# ADL5801.net
KiCad netlist of a schematic drawn in Altium Designer
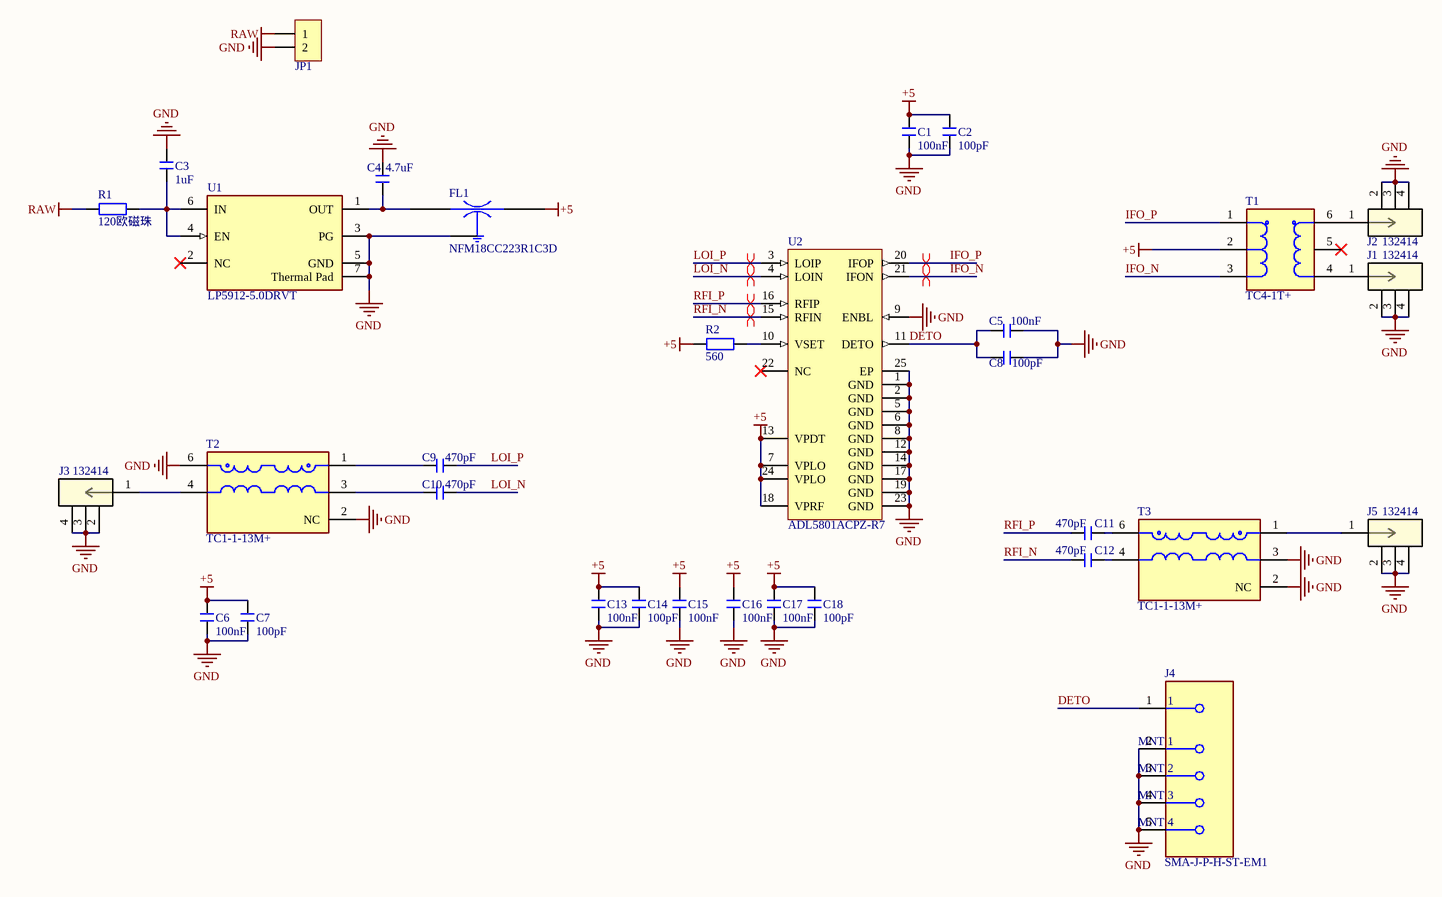
[diagram p0: ADL5801.SchDoc]

(export (version "E")
  (design (tool "Eeschema 10.0.6"))
  (components
    (comp (ref "C1")
      (value "100nF")
      (footprint "C 0402_L")
      (description "贴片电容")
      (libsource (lib "01 - 电容-电阻-电感") (part "C"))
    )
    (comp (ref "C2")
      (value "100pF")
      (footprint "C 0402_L")
      (description "贴片电容")
      (libsource (lib "01 - 电容-电阻-电感") (part "C"))
    )
    (comp (ref "C3")
      (value "1uF")
      (footprint "C 0603_L")
      (description "贴片电容")
      (libsource (lib "01 - 电容-电阻-电感") (part "C"))
    )
    (comp (ref "C4")
      (value "4.7uF")
      (footprint "C 0603_L")
      (description "贴片电容")
      (libsource (lib "01 - 电容-电阻-电感") (part "C"))
    )
    (comp (ref "C5")
      (value "100nF")
      (footprint "C 0402_L")
      (description "贴片电容")
      (libsource (lib "01 - 电容-电阻-电感") (part "C"))
    )
    (comp (ref "C6")
      (value "100nF")
      (footprint "C 0402_L")
      (description "贴片电容")
      (libsource (lib "01 - 电容-电阻-电感") (part "C"))
    )
    (comp (ref "C7")
      (value "100pF")
      (footprint "C 0402_L")
      (description "贴片电容")
      (libsource (lib "01 - 电容-电阻-电感") (part "C"))
    )
    (comp (ref "C8")
      (value "100pF")
      (footprint "C 0402_L")
      (description "贴片电容")
      (libsource (lib "01 - 电容-电阻-电感") (part "C"))
    )
    (comp (ref "C9")
      (value "470pF")
      (footprint "C 0402_L")
      (description "贴片电容")
      (libsource (lib "01 - 电容-电阻-电感") (part "C"))
    )
    (comp (ref "C10")
      (value "470pF")
      (footprint "C 0402_L")
      (description "贴片电容")
      (libsource (lib "01 - 电容-电阻-电感") (part "C"))
    )
    (comp (ref "C11")
      (value "470pF")
      (footprint "C 0402_L")
      (description "贴片电容")
      (libsource (lib "01 - 电容-电阻-电感") (part "C"))
    )
    (comp (ref "C12")
      (value "470pF")
      (footprint "C 0402_L")
      (description "贴片电容")
      (libsource (lib "01 - 电容-电阻-电感") (part "C"))
    )
    (comp (ref "C13")
      (value "100nF")
      (footprint "C 0402_L")
      (description "贴片电容")
      (libsource (lib "01 - 电容-电阻-电感") (part "C"))
    )
    (comp (ref "C14")
      (value "100pF")
      (footprint "C 0402_L")
      (description "贴片电容")
      (libsource (lib "01 - 电容-电阻-电感") (part "C"))
    )
    (comp (ref "C15")
      (value "100nF")
      (footprint "C 0402_L")
      (description "贴片电容")
      (libsource (lib "01 - 电容-电阻-电感") (part "C"))
    )
    (comp (ref "C16")
      (value "100nF")
      (footprint "C 0402_L")
      (description "贴片电容")
      (libsource (lib "01 - 电容-电阻-电感") (part "C"))
    )
    (comp (ref "C17")
      (value "100nF")
      (footprint "C 0402_L")
      (description "贴片电容")
      (libsource (lib "01 - 电容-电阻-电感") (part "C"))
    )
    (comp (ref "C18")
      (value "100pF")
      (footprint "C 0402_L")
      (description "贴片电容")
      (libsource (lib "01 - 电容-电阻-电感") (part "C"))
    )
    (comp (ref "FL1")
      (value "NFM18CC223R1C3D")
      (footprint "FIL_NFM18CC223R1C3D")
      (description "SMD Capacitor with Capacitance: 22000pF Tol. 20%. Rated Voltage: 16Vdc")
      (fields (field (name "MF") "Murata"))
      (libsource (lib "NFM18CC223R1C3D") (part "NFM18CC223R1C3D"))
    )
    (comp (ref "J1")
      (value "132414")
      (footprint "CONN_132414_AMP")
      (description "No Description Available")
      (fields (field (name "COPYRIGHT") "Copyright (C) 2022 Ultra Librarian. All rights reserved."))
      (libsource (lib "") (part "132414_2"))
    )
    (comp (ref "J2")
      (value "132414")
      (footprint "CONN_132414_AMP")
      (description "No Description Available")
      (fields (field (name "COPYRIGHT") "Copyright (C) 2022 Ultra Librarian. All rights reserved."))
      (libsource (lib "") (part "132414_1"))
    )
    (comp (ref "J3")
      (value "132414")
      (footprint "CONN_132414_AMP")
      (description "No Description Available")
      (fields (field (name "COPYRIGHT") "Copyright (C) 2022 Ultra Librarian. All rights reserved."))
      (libsource (lib "细针大偏脚SMA(用这个)") (part "132414"))
    )
    (comp (ref "J4")
      (value "SMA-J-P-H-ST-EM1")
      (footprint "FP-SMA-J-P-H-ST-EM1-MFG")
      (description "CONN SMA JACK STR 50OHM EDGE MNT")
      (libsource (lib "Altium Content Vault") (part "c65b8a639cdaef1819ea20b5466f8fa"))
    )
    (comp (ref "J5")
      (value "132414")
      (footprint "CONN_132414_AMP")
      (description "No Description Available")
      (fields (field (name "COPYRIGHT") "Copyright (C) 2022 Ultra Librarian. All rights reserved."))
      (libsource (lib "") (part "132414_2"))
    )
    (comp (ref "JP1")
      (value "HDR-1X2")
      (footprint "KF2510-LI-2P")
      (description "2P接插件")
      (libsource (lib "18 - 接插件-脚距2.54mm (100mil) ") (part "Header 2"))
    )
    (comp (ref "R1")
      (value "120欧磁珠")
      (footprint "R 0603_L")
      (description "贴片电阻")
      (libsource (lib "01 - 电容-电阻-电感") (part "R"))
    )
    (comp (ref "R2")
      (value "560")
      (footprint "R 0402_L")
      (description "贴片电阻")
      (libsource (lib "01 - 电容-电阻-电感") (part "R"))
    )
    (comp (ref "T1")
      (value "TC4-1T+")
      (footprint "TC4-1T+-Footprint-1")
      (description "Xfmr, Isolation, 50 ohm, 4: 1, 0.5-300 MHz, SMT")
      (libsource (lib "TC4-1T+") (part "TC4-1T+"))
    )
    (comp (ref "T2")
      (value "TC1-1-13M+")
      (footprint "FP-TC1-1-13M+-MFG")
      (description "RF Transformer 1: 1 5 Terminal SMD")
      (libsource (lib "DigiPCBA Workspace") (part "bfcd2037c1656edfb93934ecf7289be"))
    )
    (comp (ref "T3")
      (value "TC1-1-13M+")
      (footprint "FP-TC1-1-13M+-MFG")
      (description "RF Transformer 1: 1 5 Terminal SMD")
      (libsource (lib "DigiPCBA Workspace") (part "bfcd2037c1656edfb93934ecf7289be"))
    )
    (comp (ref "U1")
      (value "LP5912-5.0DRVT")
      (footprint "FP-DRV0006A-IPC_C")
      (description "Linear Voltage Regulator IC Positive Fixed 1 Output 5.0V 500mA 6-SON (2x2)")
      (libsource (lib "DigiPCBA Workspace") (part "2f44a6c2e9bad9ae6b461b33d08ca99"))
    )
    (comp (ref "U2")
      (value "ADL5801ACPZ-R7")
      (footprint "ADI-CP-24-3_M")
      (description "RF Mixer IC Cellular Up/Down Converter 10MHz ~ 6GHz 24-LFCSP-VQ (4x4)")
      (libsource (lib "DigiPCBA Workspace") (part "ADI-ADL5801-CP-24-3"))
    )
  )
  (nets
    (net (code "1") (name "+5") (class "Default")
      (node (ref "C1") (pin "2") (pinfunction "2_2") (pintype "passive"))
      (node (ref "C13") (pin "2") (pinfunction "2_2") (pintype "passive"))
      (node (ref "C14") (pin "2") (pinfunction "2_2") (pintype "passive"))
      (node (ref "C15") (pin "2") (pinfunction "2_2") (pintype "passive"))
      (node (ref "C16") (pin "2") (pinfunction "2_2") (pintype "passive"))
      (node (ref "C17") (pin "2") (pinfunction "2_2") (pintype "passive"))
      (node (ref "C18") (pin "2") (pinfunction "2_2") (pintype "passive"))
      (node (ref "C2") (pin "2") (pinfunction "2_2") (pintype "passive"))
      (node (ref "C6") (pin "2") (pinfunction "2_2") (pintype "passive"))
      (node (ref "C7") (pin "2") (pinfunction "2_2") (pintype "passive"))
      (node (ref "FL1") (pin "3") (pintype "passive"))
      (node (ref "R2") (pin "1") (pinfunction "1_1") (pintype "passive"))
      (node (ref "T1") (pin "2") (pinfunction "SECONDARY_2") (pintype "passive"))
      (node (ref "U2") (pin "13") (pinfunction "VPDT_13") (pintype "power_in"))
      (node (ref "U2") (pin "18") (pinfunction "VPRF_18") (pintype "power_in"))
      (node (ref "U2") (pin "24") (pinfunction "VPLO_24") (pintype "power_in"))
      (node (ref "U2") (pin "7") (pinfunction "VPLO_7") (pintype "power_in"))
    )
    (net (code "2") (name "/DETO") (class "Default")
      (node (ref "C5") (pin "1") (pinfunction "1_1") (pintype "passive"))
      (node (ref "C8") (pin "1") (pinfunction "1_1") (pintype "passive"))
      (node (ref "J4") (pin "1") (pinfunction "1_1") (pintype "passive"))
      (node (ref "U2") (pin "11") (pinfunction "DETO_11") (pintype "output"))
    )
    (net (code "3") (name "/IFO_N") (class "Default")
      (node (ref "T1") (pin "3") (pinfunction "SECONDARY_MID_3") (pintype "passive"))
      (node (ref "U2") (pin "21") (pinfunction "IFON_21") (pintype "output"))
    )
    (net (code "4") (name "/IFO_P") (class "Default")
      (node (ref "T1") (pin "1") (pinfunction "SECONDARY_DOT_1") (pintype "passive"))
      (node (ref "U2") (pin "20") (pinfunction "IFOP_20") (pintype "output"))
    )
    (net (code "5") (name "/LOI_N") (class "Default")
      (node (ref "C10") (pin "2") (pinfunction "2_2") (pintype "passive"))
      (node (ref "U2") (pin "4") (pinfunction "LOIN_4") (pintype "input"))
    )
    (net (code "6") (name "/LOI_P") (class "Default")
      (node (ref "C9") (pin "2") (pinfunction "2_2") (pintype "passive"))
      (node (ref "U2") (pin "3") (pinfunction "LOIP_3") (pintype "input"))
    )
    (net (code "7") (name "/RFI_N") (class "Default")
      (node (ref "C12") (pin "1") (pinfunction "1_1") (pintype "passive"))
      (node (ref "U2") (pin "15") (pinfunction "RFIN_15") (pintype "input"))
    )
    (net (code "8") (name "/RFI_P") (class "Default")
      (node (ref "C11") (pin "1") (pinfunction "1_1") (pintype "passive"))
      (node (ref "U2") (pin "16") (pinfunction "RFIP_16") (pintype "input"))
    )
    (net (code "9") (name "GND") (class "Default")
      (node (ref "C1") (pin "1") (pinfunction "1_1") (pintype "passive"))
      (node (ref "C13") (pin "1") (pinfunction "1_1") (pintype "passive"))
      (node (ref "C14") (pin "1") (pinfunction "1_1") (pintype "passive"))
      (node (ref "C15") (pin "1") (pinfunction "1_1") (pintype "passive"))
      (node (ref "C16") (pin "1") (pinfunction "1_1") (pintype "passive"))
      (node (ref "C17") (pin "1") (pinfunction "1_1") (pintype "passive"))
      (node (ref "C18") (pin "1") (pinfunction "1_1") (pintype "passive"))
      (node (ref "C2") (pin "1") (pinfunction "1_1") (pintype "passive"))
      (node (ref "C3") (pin "2") (pinfunction "2_2") (pintype "passive"))
      (node (ref "C4") (pin "2") (pinfunction "2_2") (pintype "passive"))
      (node (ref "C5") (pin "2") (pinfunction "2_2") (pintype "passive"))
      (node (ref "C6") (pin "1") (pinfunction "1_1") (pintype "passive"))
      (node (ref "C7") (pin "1") (pinfunction "1_1") (pintype "passive"))
      (node (ref "C8") (pin "2") (pinfunction "2_2") (pintype "passive"))
      (node (ref "FL1") (pin "2") (pinfunction "GND_2") (pintype "power_in"))
      (node (ref "J1") (pin "2") (pinfunction "2_2") (pintype "passive"))
      (node (ref "J1") (pin "3") (pinfunction "3_3") (pintype "passive"))
      (node (ref "J1") (pin "4") (pinfunction "4_4") (pintype "passive"))
      (node (ref "J2") (pin "2") (pinfunction "2_2") (pintype "passive"))
      (node (ref "J2") (pin "3") (pinfunction "3_3") (pintype "passive"))
      (node (ref "J2") (pin "4") (pinfunction "4_4") (pintype "passive"))
      (node (ref "J3") (pin "2") (pinfunction "2_2") (pintype "passive"))
      (node (ref "J3") (pin "3") (pinfunction "3_3") (pintype "passive"))
      (node (ref "J3") (pin "4") (pinfunction "4_4") (pintype "passive"))
      (node (ref "J4") (pin "2") (pinfunction "MNT_1_2") (pintype "passive"))
      (node (ref "J4") (pin "3") (pinfunction "MNT_2_3") (pintype "passive"))
      (node (ref "J4") (pin "4") (pinfunction "MNT_3_4") (pintype "passive"))
      (node (ref "J4") (pin "5") (pinfunction "MNT_4_5") (pintype "passive"))
      (node (ref "J5") (pin "2") (pinfunction "2_2") (pintype "passive"))
      (node (ref "J5") (pin "3") (pinfunction "3_3") (pintype "passive"))
      (node (ref "J5") (pin "4") (pinfunction "4_4") (pintype "passive"))
      (node (ref "JP1") (pin "2") (pinfunction "2_2") (pintype "passive"))
      (node (ref "T2") (pin "2") (pinfunction "NC_2") (pintype "passive"))
      (node (ref "T2") (pin "6") (pinfunction "PRIMARY_DOT_6") (pintype "passive"))
      (node (ref "T3") (pin "2") (pinfunction "NC_2") (pintype "passive"))
      (node (ref "T3") (pin "3") (pinfunction "SECONDARY_3") (pintype "passive"))
      (node (ref "U1") (pin "3") (pinfunction "PG_3") (pintype "open_collector"))
      (node (ref "U1") (pin "5") (pinfunction "GND_5") (pintype "power_in"))
      (node (ref "U1") (pin "7") (pinfunction "Thermal_Pad_7") (pintype "power_in"))
      (node (ref "U2") (pin "1") (pinfunction "GND_1") (pintype "power_in"))
      (node (ref "U2") (pin "12") (pinfunction "GND_12") (pintype "power_in"))
      (node (ref "U2") (pin "14") (pinfunction "GND_14") (pintype "power_in"))
      (node (ref "U2") (pin "17") (pinfunction "GND_17") (pintype "power_in"))
      (node (ref "U2") (pin "19") (pinfunction "GND_19") (pintype "power_in"))
      (node (ref "U2") (pin "2") (pinfunction "GND_2") (pintype "power_in"))
      (node (ref "U2") (pin "23") (pinfunction "GND_23") (pintype "power_in"))
      (node (ref "U2") (pin "25") (pinfunction "EP_25") (pintype "power_in"))
      (node (ref "U2") (pin "5") (pinfunction "GND_5") (pintype "power_in"))
      (node (ref "U2") (pin "6") (pinfunction "GND_6") (pintype "power_in"))
      (node (ref "U2") (pin "8") (pinfunction "GND_8") (pintype "power_in"))
      (node (ref "U2") (pin "9") (pinfunction "ENBL_9") (pintype "input"))
    )
    (net (code "10") (name "Net-(T1-PRIMARY)") (class "Default")
      (node (ref "J1") (pin "1") (pinfunction "1_1") (pintype "passive"))
      (node (ref "T1") (pin "4") (pinfunction "PRIMARY_4") (pintype "passive"))
    )
    (net (code "11") (name "Net-(T1-PRIMARY_DOT)") (class "Default")
      (node (ref "J2") (pin "1") (pinfunction "1_1") (pintype "passive"))
      (node (ref "T1") (pin "6") (pinfunction "PRIMARY_DOT_6") (pintype "passive"))
    )
    (net (code "12") (name "Net-(T2-PRIMARY)") (class "Default")
      (node (ref "J3") (pin "1") (pinfunction "1_1") (pintype "passive"))
      (node (ref "T2") (pin "4") (pinfunction "PRIMARY_4") (pintype "passive"))
    )
    (net (code "13") (name "Net-(T2-SECONDARY)") (class "Default")
      (node (ref "C10") (pin "1") (pinfunction "1_1") (pintype "passive"))
      (node (ref "T2") (pin "3") (pinfunction "SECONDARY_3") (pintype "passive"))
    )
    (net (code "14") (name "Net-(T2-SECONDARY_DOT)") (class "Default")
      (node (ref "C9") (pin "1") (pinfunction "1_1") (pintype "passive"))
      (node (ref "T2") (pin "1") (pinfunction "SECONDARY_DOT_1") (pintype "passive"))
    )
    (net (code "15") (name "Net-(T3-PRIMARY)") (class "Default")
      (node (ref "C12") (pin "2") (pinfunction "2_2") (pintype "passive"))
      (node (ref "T3") (pin "4") (pinfunction "PRIMARY_4") (pintype "passive"))
    )
    (net (code "16") (name "Net-(T3-PRIMARY_DOT)") (class "Default")
      (node (ref "C11") (pin "2") (pinfunction "2_2") (pintype "passive"))
      (node (ref "T3") (pin "6") (pinfunction "PRIMARY_DOT_6") (pintype "passive"))
    )
    (net (code "17") (name "Net-(T3-SECONDARY_DOT)") (class "Default")
      (node (ref "J5") (pin "1") (pinfunction "1_1") (pintype "passive"))
      (node (ref "T3") (pin "1") (pinfunction "SECONDARY_DOT_1") (pintype "passive"))
    )
    (net (code "18") (name "Net-(U1-EN)") (class "Default")
      (node (ref "C3") (pin "1") (pinfunction "1_1") (pintype "passive"))
      (node (ref "R1") (pin "2") (pinfunction "2_2") (pintype "passive"))
      (node (ref "U1") (pin "4") (pinfunction "EN_4") (pintype "input"))
      (node (ref "U1") (pin "6") (pinfunction "IN_6") (pintype "power_in"))
    )
    (net (code "19") (name "Net-(U1-OUT)") (class "Default")
      (node (ref "C4") (pin "1") (pinfunction "1_1") (pintype "passive"))
      (node (ref "FL1") (pin "1") (pintype "passive"))
      (node (ref "U1") (pin "1") (pinfunction "OUT_1") (pintype "power_in"))
    )
    (net (code "20") (name "Net-(U2-VSET)") (class "Default")
      (node (ref "R2") (pin "2") (pinfunction "2_2") (pintype "passive"))
      (node (ref "U2") (pin "10") (pinfunction "VSET_10") (pintype "input"))
    )
    (net (code "21") (name "RAW") (class "Default")
      (node (ref "JP1") (pin "1") (pinfunction "1_1") (pintype "passive"))
      (node (ref "R1") (pin "1") (pinfunction "1_1") (pintype "passive"))
    )
    (net (code "22") (name "unconnected-(T1-NC-Pad5)") (class "Default")
      (node (ref "T1") (pin "5") (pinfunction "NC_5") (pintype "passive+no_connect"))
    )
    (net (code "23") (name "unconnected-(U1-NC-Pad2)") (class "Default")
      (node (ref "U1") (pin "2") (pinfunction "NC_2") (pintype "passive+no_connect"))
    )
    (net (code "24") (name "unconnected-(U2-NC-Pad22)") (class "Default")
      (node (ref "U2") (pin "22") (pinfunction "NC_22") (pintype "passive+no_connect"))
    )
  )
)
